# WL-BPF_L.net
KiCad netlist of a schematic drawn in Altium Designer
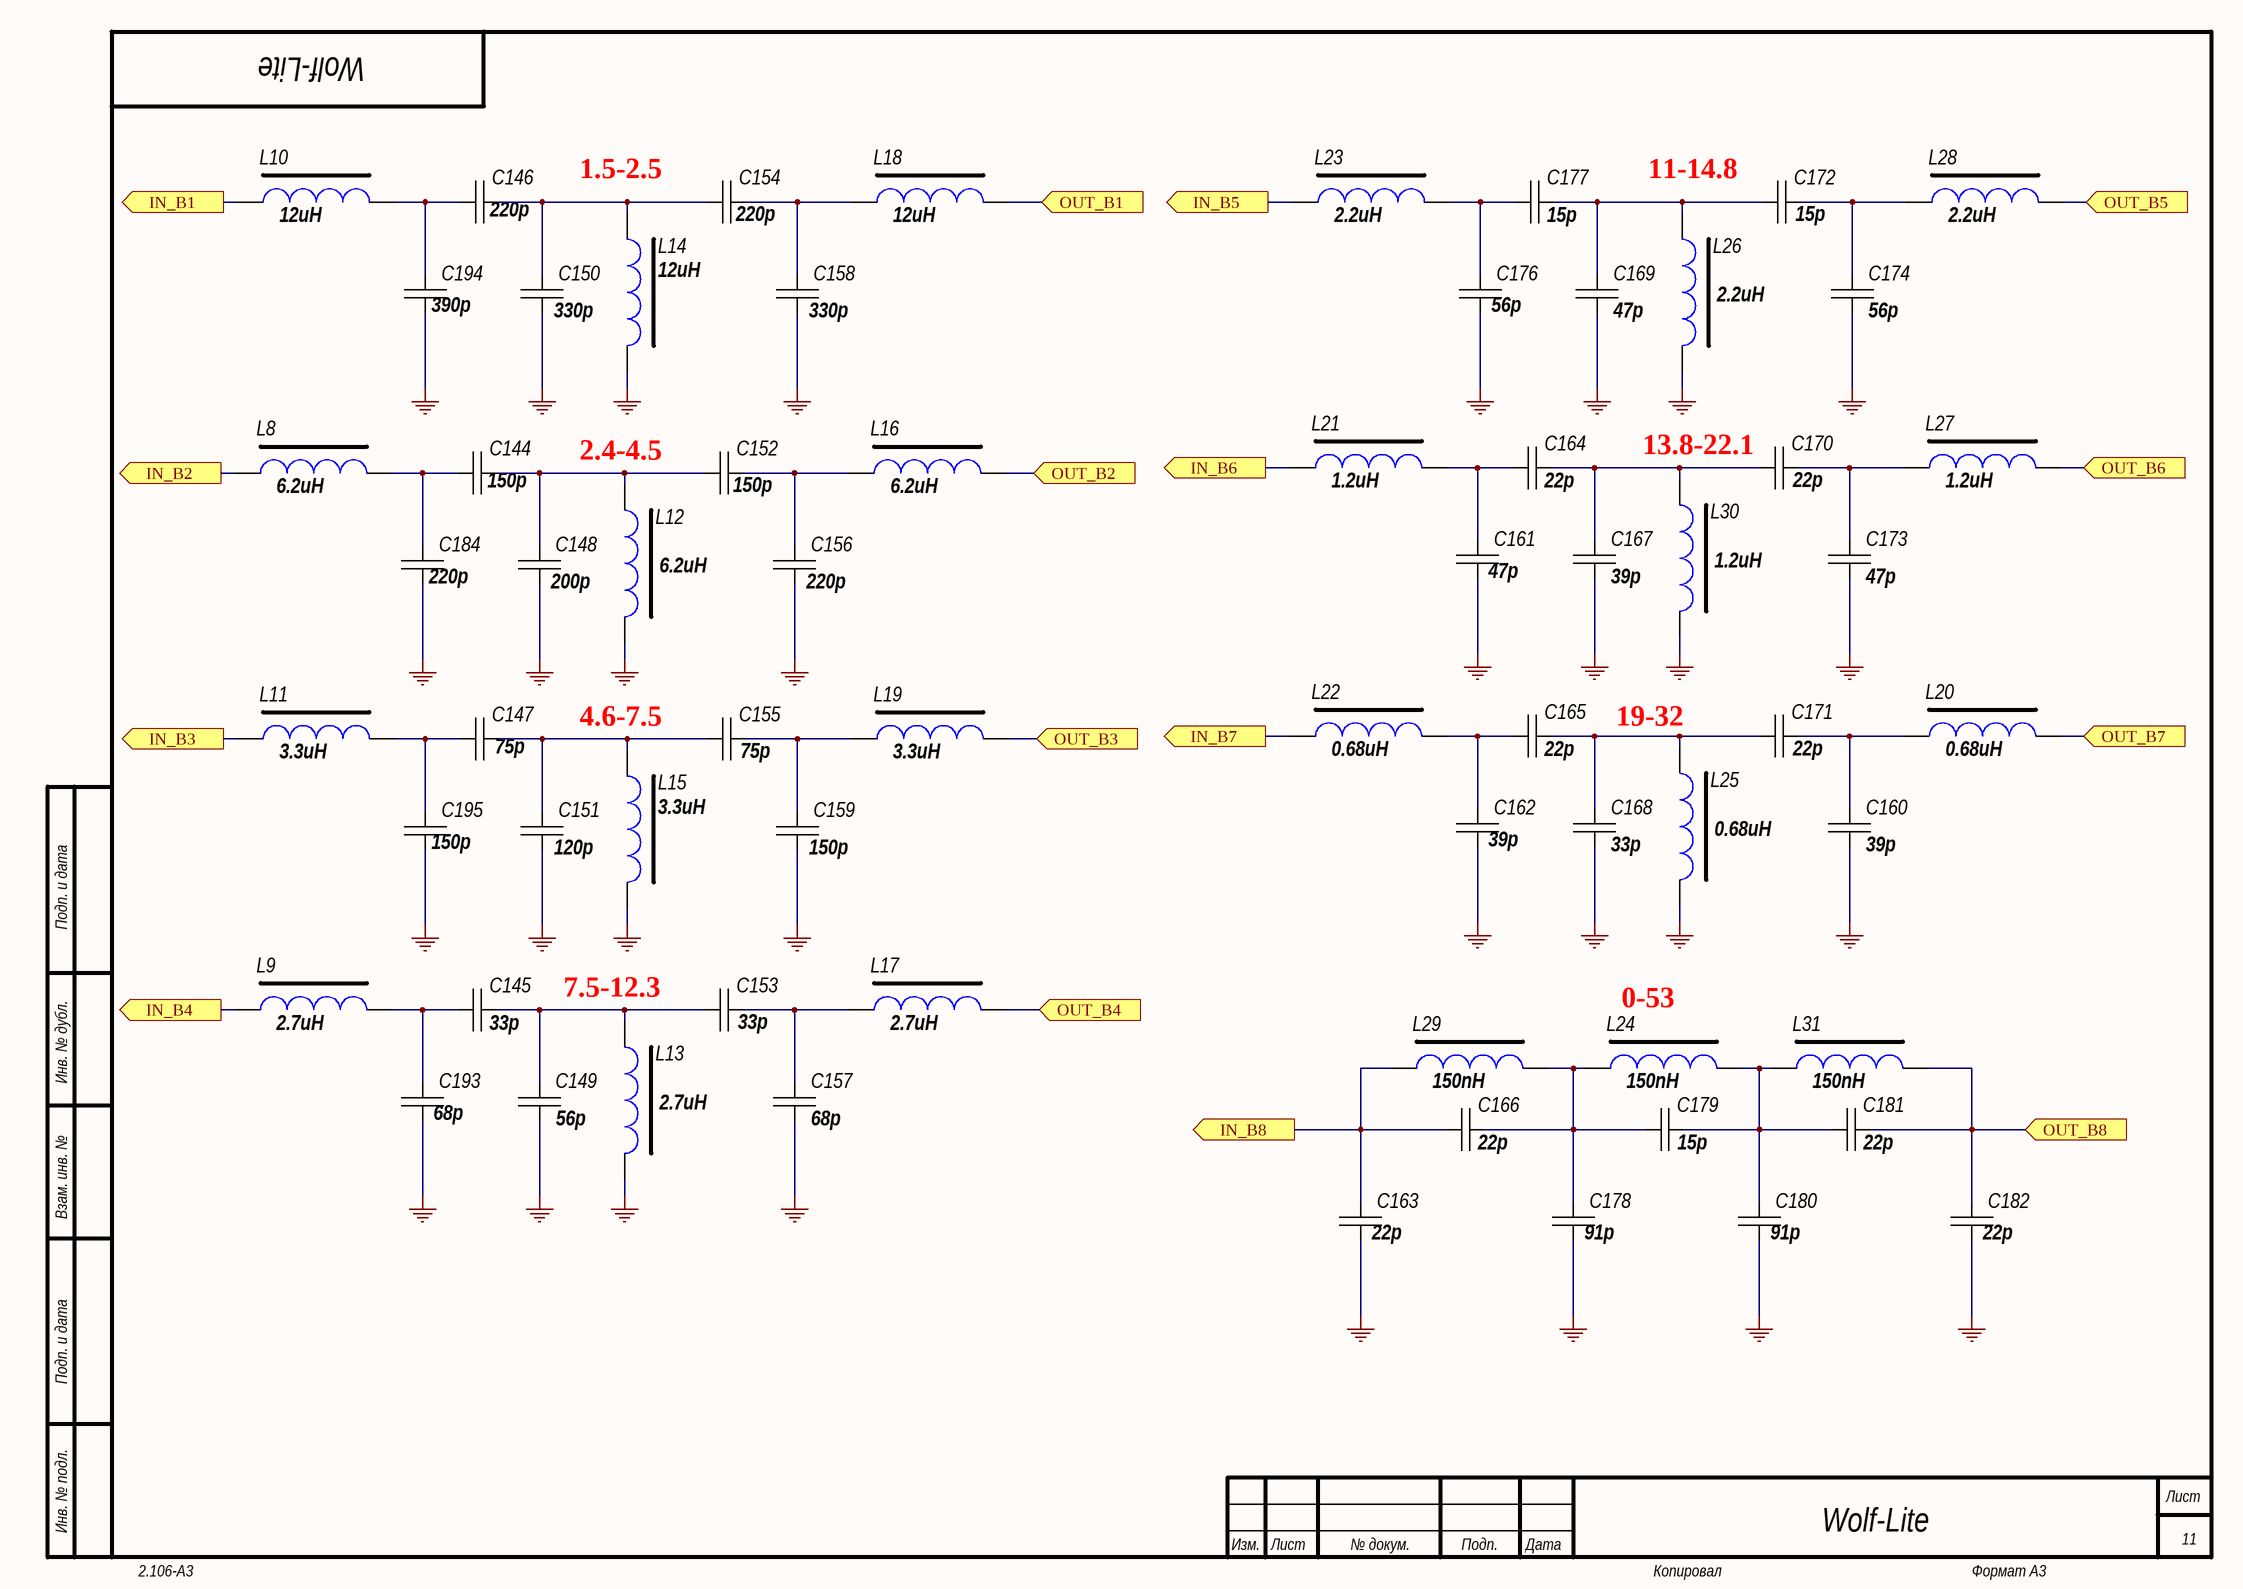
[diagram p0: WL-BPF_L.SchDoc]

(export (version "E")
  (design (tool "Eeschema 10.0.6"))
  (components
    (comp (ref "C144")
      (value "150p")
      (footprint "standard:CH0805C")
      (libsource (lib "Discrete") (part "Capacitor"))
    )
    (comp (ref "C145")
      (value "33p")
      (footprint "standard:CH0805C")
      (libsource (lib "Discrete") (part "Capacitor"))
    )
    (comp (ref "C146")
      (value "220p")
      (footprint "standard:CH0805C")
      (libsource (lib "Discrete") (part "Capacitor"))
    )
    (comp (ref "C147")
      (value "75p")
      (footprint "standard:CH0805C")
      (libsource (lib "Discrete") (part "Capacitor"))
    )
    (comp (ref "C148")
      (value "200p")
      (footprint "standard:CH0805C")
      (libsource (lib "Discrete") (part "Capacitor"))
    )
    (comp (ref "C149")
      (value "56p")
      (footprint "standard:CH0805C")
      (libsource (lib "Discrete") (part "Capacitor"))
    )
    (comp (ref "C150")
      (value "330p")
      (footprint "standard:CH0805C")
      (libsource (lib "Discrete") (part "Capacitor"))
    )
    (comp (ref "C151")
      (value "120p")
      (footprint "standard:CH0805C")
      (libsource (lib "Discrete") (part "Capacitor"))
    )
    (comp (ref "C152")
      (value "150p")
      (footprint "standard:CH0805C")
      (libsource (lib "Discrete") (part "Capacitor"))
    )
    (comp (ref "C153")
      (value "33p")
      (footprint "standard:CH0805C")
      (libsource (lib "Discrete") (part "Capacitor"))
    )
    (comp (ref "C154")
      (value "220p")
      (footprint "standard:CH0805C")
      (libsource (lib "Discrete") (part "Capacitor"))
    )
    (comp (ref "C155")
      (value "75p")
      (footprint "standard:CH0805C")
      (libsource (lib "Discrete") (part "Capacitor"))
    )
    (comp (ref "C156")
      (value "220p")
      (footprint "standard:CH0805C")
      (libsource (lib "Discrete") (part "Capacitor"))
    )
    (comp (ref "C157")
      (value "68p")
      (footprint "standard:CH0805C")
      (libsource (lib "Discrete") (part "Capacitor"))
    )
    (comp (ref "C158")
      (value "330p")
      (footprint "standard:CH0805C")
      (libsource (lib "Discrete") (part "Capacitor"))
    )
    (comp (ref "C159")
      (value "150p")
      (footprint "standard:CH0805C")
      (libsource (lib "Discrete") (part "Capacitor"))
    )
    (comp (ref "C160")
      (value "39p")
      (footprint "standard:CH0805C")
      (libsource (lib "Discrete") (part "Capacitor"))
    )
    (comp (ref "C161")
      (value "47p")
      (footprint "standard:CH0805C")
      (libsource (lib "Discrete") (part "Capacitor"))
    )
    (comp (ref "C162")
      (value "39p")
      (footprint "standard:CH0805C")
      (libsource (lib "Discrete") (part "Capacitor"))
    )
    (comp (ref "C163")
      (value "22p")
      (footprint "standard:CH0805C")
      (libsource (lib "Discrete") (part "Capacitor"))
    )
    (comp (ref "C164")
      (value "22p")
      (footprint "standard:CH0805C")
      (libsource (lib "Discrete") (part "Capacitor"))
    )
    (comp (ref "C165")
      (value "22p")
      (footprint "standard:CH0805C")
      (libsource (lib "Discrete") (part "Capacitor"))
    )
    (comp (ref "C166")
      (value "22p")
      (footprint "standard:CH0805C")
      (libsource (lib "Discrete") (part "Capacitor"))
    )
    (comp (ref "C167")
      (value "39p")
      (footprint "standard:CH0805C")
      (libsource (lib "Discrete") (part "Capacitor"))
    )
    (comp (ref "C168")
      (value "33p")
      (footprint "standard:CH0805C")
      (libsource (lib "Discrete") (part "Capacitor"))
    )
    (comp (ref "C169")
      (value "47p")
      (footprint "standard:CH0805C")
      (libsource (lib "Discrete") (part "Capacitor"))
    )
    (comp (ref "C170")
      (value "22p")
      (footprint "standard:CH0805C")
      (libsource (lib "Discrete") (part "Capacitor"))
    )
    (comp (ref "C171")
      (value "22p")
      (footprint "standard:CH0805C")
      (libsource (lib "Discrete") (part "Capacitor"))
    )
    (comp (ref "C172")
      (value "15p")
      (footprint "standard:CH0805C")
      (libsource (lib "Discrete") (part "Capacitor"))
    )
    (comp (ref "C173")
      (value "47p")
      (footprint "standard:CH0805C")
      (libsource (lib "Discrete") (part "Capacitor"))
    )
    (comp (ref "C174")
      (value "56p")
      (footprint "standard:CH0805C")
      (libsource (lib "Discrete") (part "Capacitor"))
    )
    (comp (ref "C176")
      (value "56p")
      (footprint "standard:CH0805C")
      (libsource (lib "Discrete") (part "Capacitor"))
    )
    (comp (ref "C177")
      (value "15p")
      (footprint "standard:CH0805C")
      (libsource (lib "Discrete") (part "Capacitor"))
    )
    (comp (ref "C178")
      (value "91p")
      (footprint "standard:CH0805C")
      (libsource (lib "Discrete") (part "Capacitor"))
    )
    (comp (ref "C179")
      (value "15p")
      (footprint "standard:CH0805C")
      (libsource (lib "Discrete") (part "Capacitor"))
    )
    (comp (ref "C180")
      (value "91p")
      (footprint "standard:CH0805C")
      (libsource (lib "Discrete") (part "Capacitor"))
    )
    (comp (ref "C181")
      (value "22p")
      (footprint "standard:CH0805C")
      (libsource (lib "Discrete") (part "Capacitor"))
    )
    (comp (ref "C182")
      (value "22p")
      (footprint "standard:CH0805C")
      (libsource (lib "Discrete") (part "Capacitor"))
    )
    (comp (ref "C184")
      (value "220p")
      (footprint "standard:CH0805C")
      (libsource (lib "Discrete") (part "Capacitor"))
    )
    (comp (ref "C193")
      (value "68p")
      (footprint "standard:CH0805C")
      (libsource (lib "Discrete") (part "Capacitor"))
    )
    (comp (ref "C194")
      (value "390p")
      (footprint "standard:CH0805C")
      (libsource (lib "Discrete") (part "Capacitor"))
    )
    (comp (ref "C195")
      (value "150p")
      (footprint "standard:CH0805C")
      (libsource (lib "Discrete") (part "Capacitor"))
    )
    (comp (ref "L8") (value "6.2uH") (footprint "L1210") (libsource (lib "Transformers") (part "TRANS")))
    (comp (ref "L9") (value "2.7uH") (footprint "L1210") (libsource (lib "Transformers") (part "TRANS")))
    (comp (ref "L10") (value "12uH") (footprint "L1210") (libsource (lib "Transformers") (part "TRANS")))
    (comp (ref "L11") (value "3.3uH") (footprint "L1210") (libsource (lib "Transformers") (part "TRANS")))
    (comp (ref "L12") (value "6.2uH") (footprint "L1210") (libsource (lib "") (part "TRANS_1")))
    (comp (ref "L13") (value "2.7uH") (footprint "L1210") (libsource (lib "") (part "TRANS_1")))
    (comp (ref "L14") (value "12uH") (footprint "L1210") (libsource (lib "") (part "TRANS_1")))
    (comp (ref "L15") (value "3.3uH") (footprint "L1210") (libsource (lib "") (part "TRANS_1")))
    (comp (ref "L16") (value "6.2uH") (footprint "L1210") (libsource (lib "Transformers") (part "TRANS")))
    (comp (ref "L17") (value "2.7uH") (footprint "L1210") (libsource (lib "Transformers") (part "TRANS")))
    (comp (ref "L18") (value "12uH") (footprint "L1210") (libsource (lib "Transformers") (part "TRANS")))
    (comp (ref "L19") (value "3.3uH") (footprint "L1210") (libsource (lib "Transformers") (part "TRANS")))
    (comp (ref "L20") (value "0.68uH") (footprint "L1210") (libsource (lib "Transformers") (part "TRANS")))
    (comp (ref "L21") (value "1.2uH") (footprint "L1210") (libsource (lib "Transformers") (part "TRANS")))
    (comp (ref "L22") (value "0.68uH") (footprint "L1210") (libsource (lib "Transformers") (part "TRANS")))
    (comp (ref "L23") (value "2.2uH") (footprint "L1210") (libsource (lib "Transformers") (part "TRANS")))
    (comp (ref "L24") (value "150nH") (footprint "L1210") (libsource (lib "Transformers") (part "TRANS")))
    (comp (ref "L25") (value "0.68uH") (footprint "L1210") (libsource (lib "") (part "TRANS_1")))
    (comp (ref "L26") (value "2.2uH") (footprint "L1210") (libsource (lib "") (part "TRANS_1")))
    (comp (ref "L27") (value "1.2uH") (footprint "L1210") (libsource (lib "Transformers") (part "TRANS")))
    (comp (ref "L28") (value "2.2uH") (footprint "L1210") (libsource (lib "Transformers") (part "TRANS")))
    (comp (ref "L29") (value "150nH") (footprint "L1210") (libsource (lib "Transformers") (part "TRANS")))
    (comp (ref "L30") (value "1.2uH") (footprint "L1210") (libsource (lib "") (part "TRANS_1")))
    (comp (ref "L31") (value "150nH") (footprint "L1210") (libsource (lib "Transformers") (part "TRANS")))
  )
  (nets
    (net (code "1") (name "/IN_B1") (class "Default")
      (node (ref "L10") (pin "1") (pinfunction "1_1") (pintype "power_in"))
    )
    (net (code "2") (name "/IN_B2") (class "Default")
      (node (ref "L8") (pin "1") (pinfunction "1_1") (pintype "power_in"))
    )
    (net (code "3") (name "/IN_B3") (class "Default")
      (node (ref "L11") (pin "1") (pinfunction "1_1") (pintype "power_in"))
    )
    (net (code "4") (name "/IN_B4") (class "Default")
      (node (ref "L9") (pin "1") (pinfunction "1_1") (pintype "power_in"))
    )
    (net (code "5") (name "/IN_B5") (class "Default")
      (node (ref "L23") (pin "1") (pinfunction "1_1") (pintype "power_in"))
    )
    (net (code "6") (name "/IN_B6") (class "Default")
      (node (ref "L21") (pin "1") (pinfunction "1_1") (pintype "power_in"))
    )
    (net (code "7") (name "/IN_B7") (class "Default")
      (node (ref "L22") (pin "1") (pinfunction "1_1") (pintype "power_in"))
    )
    (net (code "8") (name "/IN_B8") (class "Default")
      (node (ref "C163") (pin "2") (pinfunction "2_2") (pintype "power_in"))
      (node (ref "C166") (pin "1") (pinfunction "1_1") (pintype "power_in"))
      (node (ref "L29") (pin "1") (pinfunction "1_1") (pintype "power_in"))
    )
    (net (code "9") (name "/OUT_B1") (class "Default")
      (node (ref "L18") (pin "2") (pinfunction "2_2") (pintype "power_in"))
    )
    (net (code "10") (name "/OUT_B2") (class "Default")
      (node (ref "L16") (pin "2") (pinfunction "2_2") (pintype "power_in"))
    )
    (net (code "11") (name "/OUT_B3") (class "Default")
      (node (ref "L19") (pin "2") (pinfunction "2_2") (pintype "power_in"))
    )
    (net (code "12") (name "/OUT_B4") (class "Default")
      (node (ref "L17") (pin "2") (pinfunction "2_2") (pintype "power_in"))
    )
    (net (code "13") (name "/OUT_B5") (class "Default")
      (node (ref "L28") (pin "2") (pinfunction "2_2") (pintype "power_in"))
    )
    (net (code "14") (name "/OUT_B6") (class "Default")
      (node (ref "L27") (pin "2") (pinfunction "2_2") (pintype "power_in"))
    )
    (net (code "15") (name "/OUT_B7") (class "Default")
      (node (ref "L20") (pin "2") (pinfunction "2_2") (pintype "power_in"))
    )
    (net (code "16") (name "/OUT_B8") (class "Default")
      (node (ref "C181") (pin "2") (pinfunction "2_2") (pintype "power_in"))
      (node (ref "C182") (pin "2") (pinfunction "2_2") (pintype "power_in"))
      (node (ref "L31") (pin "2") (pinfunction "2_2") (pintype "power_in"))
    )
    (net (code "17") (name "GND") (class "Default")
      (node (ref "C148") (pin "1") (pinfunction "1_1") (pintype "power_in"))
      (node (ref "C149") (pin "1") (pinfunction "1_1") (pintype "power_in"))
      (node (ref "C150") (pin "1") (pinfunction "1_1") (pintype "power_in"))
      (node (ref "C151") (pin "1") (pinfunction "1_1") (pintype "power_in"))
      (node (ref "C156") (pin "1") (pinfunction "1_1") (pintype "power_in"))
      (node (ref "C157") (pin "1") (pinfunction "1_1") (pintype "power_in"))
      (node (ref "C158") (pin "1") (pinfunction "1_1") (pintype "power_in"))
      (node (ref "C159") (pin "1") (pinfunction "1_1") (pintype "power_in"))
      (node (ref "C160") (pin "1") (pinfunction "1_1") (pintype "power_in"))
      (node (ref "C161") (pin "1") (pinfunction "1_1") (pintype "power_in"))
      (node (ref "C162") (pin "1") (pinfunction "1_1") (pintype "power_in"))
      (node (ref "C163") (pin "1") (pinfunction "1_1") (pintype "power_in"))
      (node (ref "C167") (pin "1") (pinfunction "1_1") (pintype "power_in"))
      (node (ref "C168") (pin "1") (pinfunction "1_1") (pintype "power_in"))
      (node (ref "C169") (pin "1") (pinfunction "1_1") (pintype "power_in"))
      (node (ref "C173") (pin "1") (pinfunction "1_1") (pintype "power_in"))
      (node (ref "C174") (pin "1") (pinfunction "1_1") (pintype "power_in"))
      (node (ref "C176") (pin "1") (pinfunction "1_1") (pintype "power_in"))
      (node (ref "C178") (pin "1") (pinfunction "1_1") (pintype "power_in"))
      (node (ref "C180") (pin "1") (pinfunction "1_1") (pintype "power_in"))
      (node (ref "C182") (pin "1") (pinfunction "1_1") (pintype "power_in"))
      (node (ref "C184") (pin "1") (pinfunction "1_1") (pintype "power_in"))
      (node (ref "C193") (pin "1") (pinfunction "1_1") (pintype "power_in"))
      (node (ref "C194") (pin "1") (pinfunction "1_1") (pintype "power_in"))
      (node (ref "C195") (pin "1") (pinfunction "1_1") (pintype "power_in"))
      (node (ref "L12") (pin "1") (pinfunction "1_1") (pintype "power_in"))
      (node (ref "L13") (pin "1") (pinfunction "1_1") (pintype "power_in"))
      (node (ref "L14") (pin "1") (pinfunction "1_1") (pintype "power_in"))
      (node (ref "L15") (pin "1") (pinfunction "1_1") (pintype "power_in"))
      (node (ref "L25") (pin "1") (pinfunction "1_1") (pintype "power_in"))
      (node (ref "L26") (pin "1") (pinfunction "1_1") (pintype "power_in"))
      (node (ref "L30") (pin "1") (pinfunction "1_1") (pintype "power_in"))
    )
    (net (code "18") (name "Net-(C144-Pad1)") (class "Default")
      (node (ref "C144") (pin "1") (pinfunction "1_1") (pintype "power_in"))
      (node (ref "C184") (pin "2") (pinfunction "2_2") (pintype "power_in"))
      (node (ref "L8") (pin "2") (pinfunction "2_2") (pintype "power_in"))
    )
    (net (code "19") (name "Net-(C144-Pad2)") (class "Default")
      (node (ref "C144") (pin "2") (pinfunction "2_2") (pintype "power_in"))
      (node (ref "C148") (pin "2") (pinfunction "2_2") (pintype "power_in"))
      (node (ref "C152") (pin "1") (pinfunction "1_1") (pintype "power_in"))
      (node (ref "L12") (pin "2") (pinfunction "2_2") (pintype "power_in"))
    )
    (net (code "20") (name "Net-(C145-Pad1)") (class "Default")
      (node (ref "C145") (pin "1") (pinfunction "1_1") (pintype "power_in"))
      (node (ref "C193") (pin "2") (pinfunction "2_2") (pintype "power_in"))
      (node (ref "L9") (pin "2") (pinfunction "2_2") (pintype "power_in"))
    )
    (net (code "21") (name "Net-(C145-Pad2)") (class "Default")
      (node (ref "C145") (pin "2") (pinfunction "2_2") (pintype "power_in"))
      (node (ref "C149") (pin "2") (pinfunction "2_2") (pintype "power_in"))
      (node (ref "C153") (pin "1") (pinfunction "1_1") (pintype "power_in"))
      (node (ref "L13") (pin "2") (pinfunction "2_2") (pintype "power_in"))
    )
    (net (code "22") (name "Net-(C146-Pad1)") (class "Default")
      (node (ref "C146") (pin "1") (pinfunction "1_1") (pintype "power_in"))
      (node (ref "C194") (pin "2") (pinfunction "2_2") (pintype "power_in"))
      (node (ref "L10") (pin "2") (pinfunction "2_2") (pintype "power_in"))
    )
    (net (code "23") (name "Net-(C146-Pad2)") (class "Default")
      (node (ref "C146") (pin "2") (pinfunction "2_2") (pintype "power_in"))
      (node (ref "C150") (pin "2") (pinfunction "2_2") (pintype "power_in"))
      (node (ref "C154") (pin "1") (pinfunction "1_1") (pintype "power_in"))
      (node (ref "L14") (pin "2") (pinfunction "2_2") (pintype "power_in"))
    )
    (net (code "24") (name "Net-(C147-Pad1)") (class "Default")
      (node (ref "C147") (pin "1") (pinfunction "1_1") (pintype "power_in"))
      (node (ref "C195") (pin "2") (pinfunction "2_2") (pintype "power_in"))
      (node (ref "L11") (pin "2") (pinfunction "2_2") (pintype "power_in"))
    )
    (net (code "25") (name "Net-(C147-Pad2)") (class "Default")
      (node (ref "C147") (pin "2") (pinfunction "2_2") (pintype "power_in"))
      (node (ref "C151") (pin "2") (pinfunction "2_2") (pintype "power_in"))
      (node (ref "C155") (pin "1") (pinfunction "1_1") (pintype "power_in"))
      (node (ref "L15") (pin "2") (pinfunction "2_2") (pintype "power_in"))
    )
    (net (code "26") (name "Net-(C152-Pad2)") (class "Default")
      (node (ref "C152") (pin "2") (pinfunction "2_2") (pintype "power_in"))
      (node (ref "C156") (pin "2") (pinfunction "2_2") (pintype "power_in"))
      (node (ref "L16") (pin "1") (pinfunction "1_1") (pintype "power_in"))
    )
    (net (code "27") (name "Net-(C153-Pad2)") (class "Default")
      (node (ref "C153") (pin "2") (pinfunction "2_2") (pintype "power_in"))
      (node (ref "C157") (pin "2") (pinfunction "2_2") (pintype "power_in"))
      (node (ref "L17") (pin "1") (pinfunction "1_1") (pintype "power_in"))
    )
    (net (code "28") (name "Net-(C154-Pad2)") (class "Default")
      (node (ref "C154") (pin "2") (pinfunction "2_2") (pintype "power_in"))
      (node (ref "C158") (pin "2") (pinfunction "2_2") (pintype "power_in"))
      (node (ref "L18") (pin "1") (pinfunction "1_1") (pintype "power_in"))
    )
    (net (code "29") (name "Net-(C155-Pad2)") (class "Default")
      (node (ref "C155") (pin "2") (pinfunction "2_2") (pintype "power_in"))
      (node (ref "C159") (pin "2") (pinfunction "2_2") (pintype "power_in"))
      (node (ref "L19") (pin "1") (pinfunction "1_1") (pintype "power_in"))
    )
    (net (code "30") (name "Net-(C160-Pad2)") (class "Default")
      (node (ref "C160") (pin "2") (pinfunction "2_2") (pintype "power_in"))
      (node (ref "C171") (pin "2") (pinfunction "2_2") (pintype "power_in"))
      (node (ref "L20") (pin "1") (pinfunction "1_1") (pintype "power_in"))
    )
    (net (code "31") (name "Net-(C161-Pad2)") (class "Default")
      (node (ref "C161") (pin "2") (pinfunction "2_2") (pintype "power_in"))
      (node (ref "C164") (pin "1") (pinfunction "1_1") (pintype "power_in"))
      (node (ref "L21") (pin "2") (pinfunction "2_2") (pintype "power_in"))
    )
    (net (code "32") (name "Net-(C162-Pad2)") (class "Default")
      (node (ref "C162") (pin "2") (pinfunction "2_2") (pintype "power_in"))
      (node (ref "C165") (pin "1") (pinfunction "1_1") (pintype "power_in"))
      (node (ref "L22") (pin "2") (pinfunction "2_2") (pintype "power_in"))
    )
    (net (code "33") (name "Net-(C164-Pad2)") (class "Default")
      (node (ref "C164") (pin "2") (pinfunction "2_2") (pintype "power_in"))
      (node (ref "C167") (pin "2") (pinfunction "2_2") (pintype "power_in"))
      (node (ref "C170") (pin "1") (pinfunction "1_1") (pintype "power_in"))
      (node (ref "L30") (pin "2") (pinfunction "2_2") (pintype "power_in"))
    )
    (net (code "34") (name "Net-(C165-Pad2)") (class "Default")
      (node (ref "C165") (pin "2") (pinfunction "2_2") (pintype "power_in"))
      (node (ref "C168") (pin "2") (pinfunction "2_2") (pintype "power_in"))
      (node (ref "C171") (pin "1") (pinfunction "1_1") (pintype "power_in"))
      (node (ref "L25") (pin "2") (pinfunction "2_2") (pintype "power_in"))
    )
    (net (code "35") (name "Net-(C166-Pad2)") (class "Default")
      (node (ref "C166") (pin "2") (pinfunction "2_2") (pintype "power_in"))
      (node (ref "C178") (pin "2") (pinfunction "2_2") (pintype "power_in"))
      (node (ref "C179") (pin "1") (pinfunction "1_1") (pintype "power_in"))
      (node (ref "L24") (pin "1") (pinfunction "1_1") (pintype "power_in"))
      (node (ref "L29") (pin "2") (pinfunction "2_2") (pintype "power_in"))
    )
    (net (code "36") (name "Net-(C169-Pad2)") (class "Default")
      (node (ref "C169") (pin "2") (pinfunction "2_2") (pintype "power_in"))
      (node (ref "C172") (pin "1") (pinfunction "1_1") (pintype "power_in"))
      (node (ref "C177") (pin "2") (pinfunction "2_2") (pintype "power_in"))
      (node (ref "L26") (pin "2") (pinfunction "2_2") (pintype "power_in"))
    )
    (net (code "37") (name "Net-(C170-Pad2)") (class "Default")
      (node (ref "C170") (pin "2") (pinfunction "2_2") (pintype "power_in"))
      (node (ref "C173") (pin "2") (pinfunction "2_2") (pintype "power_in"))
      (node (ref "L27") (pin "1") (pinfunction "1_1") (pintype "power_in"))
    )
    (net (code "38") (name "Net-(C172-Pad2)") (class "Default")
      (node (ref "C172") (pin "2") (pinfunction "2_2") (pintype "power_in"))
      (node (ref "C174") (pin "2") (pinfunction "2_2") (pintype "power_in"))
      (node (ref "L28") (pin "1") (pinfunction "1_1") (pintype "power_in"))
    )
    (net (code "39") (name "Net-(C176-Pad2)") (class "Default")
      (node (ref "C176") (pin "2") (pinfunction "2_2") (pintype "power_in"))
      (node (ref "C177") (pin "1") (pinfunction "1_1") (pintype "power_in"))
      (node (ref "L23") (pin "2") (pinfunction "2_2") (pintype "power_in"))
    )
    (net (code "40") (name "Net-(C179-Pad2)") (class "Default")
      (node (ref "C179") (pin "2") (pinfunction "2_2") (pintype "power_in"))
      (node (ref "C180") (pin "2") (pinfunction "2_2") (pintype "power_in"))
      (node (ref "C181") (pin "1") (pinfunction "1_1") (pintype "power_in"))
      (node (ref "L24") (pin "2") (pinfunction "2_2") (pintype "power_in"))
      (node (ref "L31") (pin "1") (pinfunction "1_1") (pintype "power_in"))
    )
  )
)
